# M401H.net
KiCad netlist of a schematic drawn in EAGLE
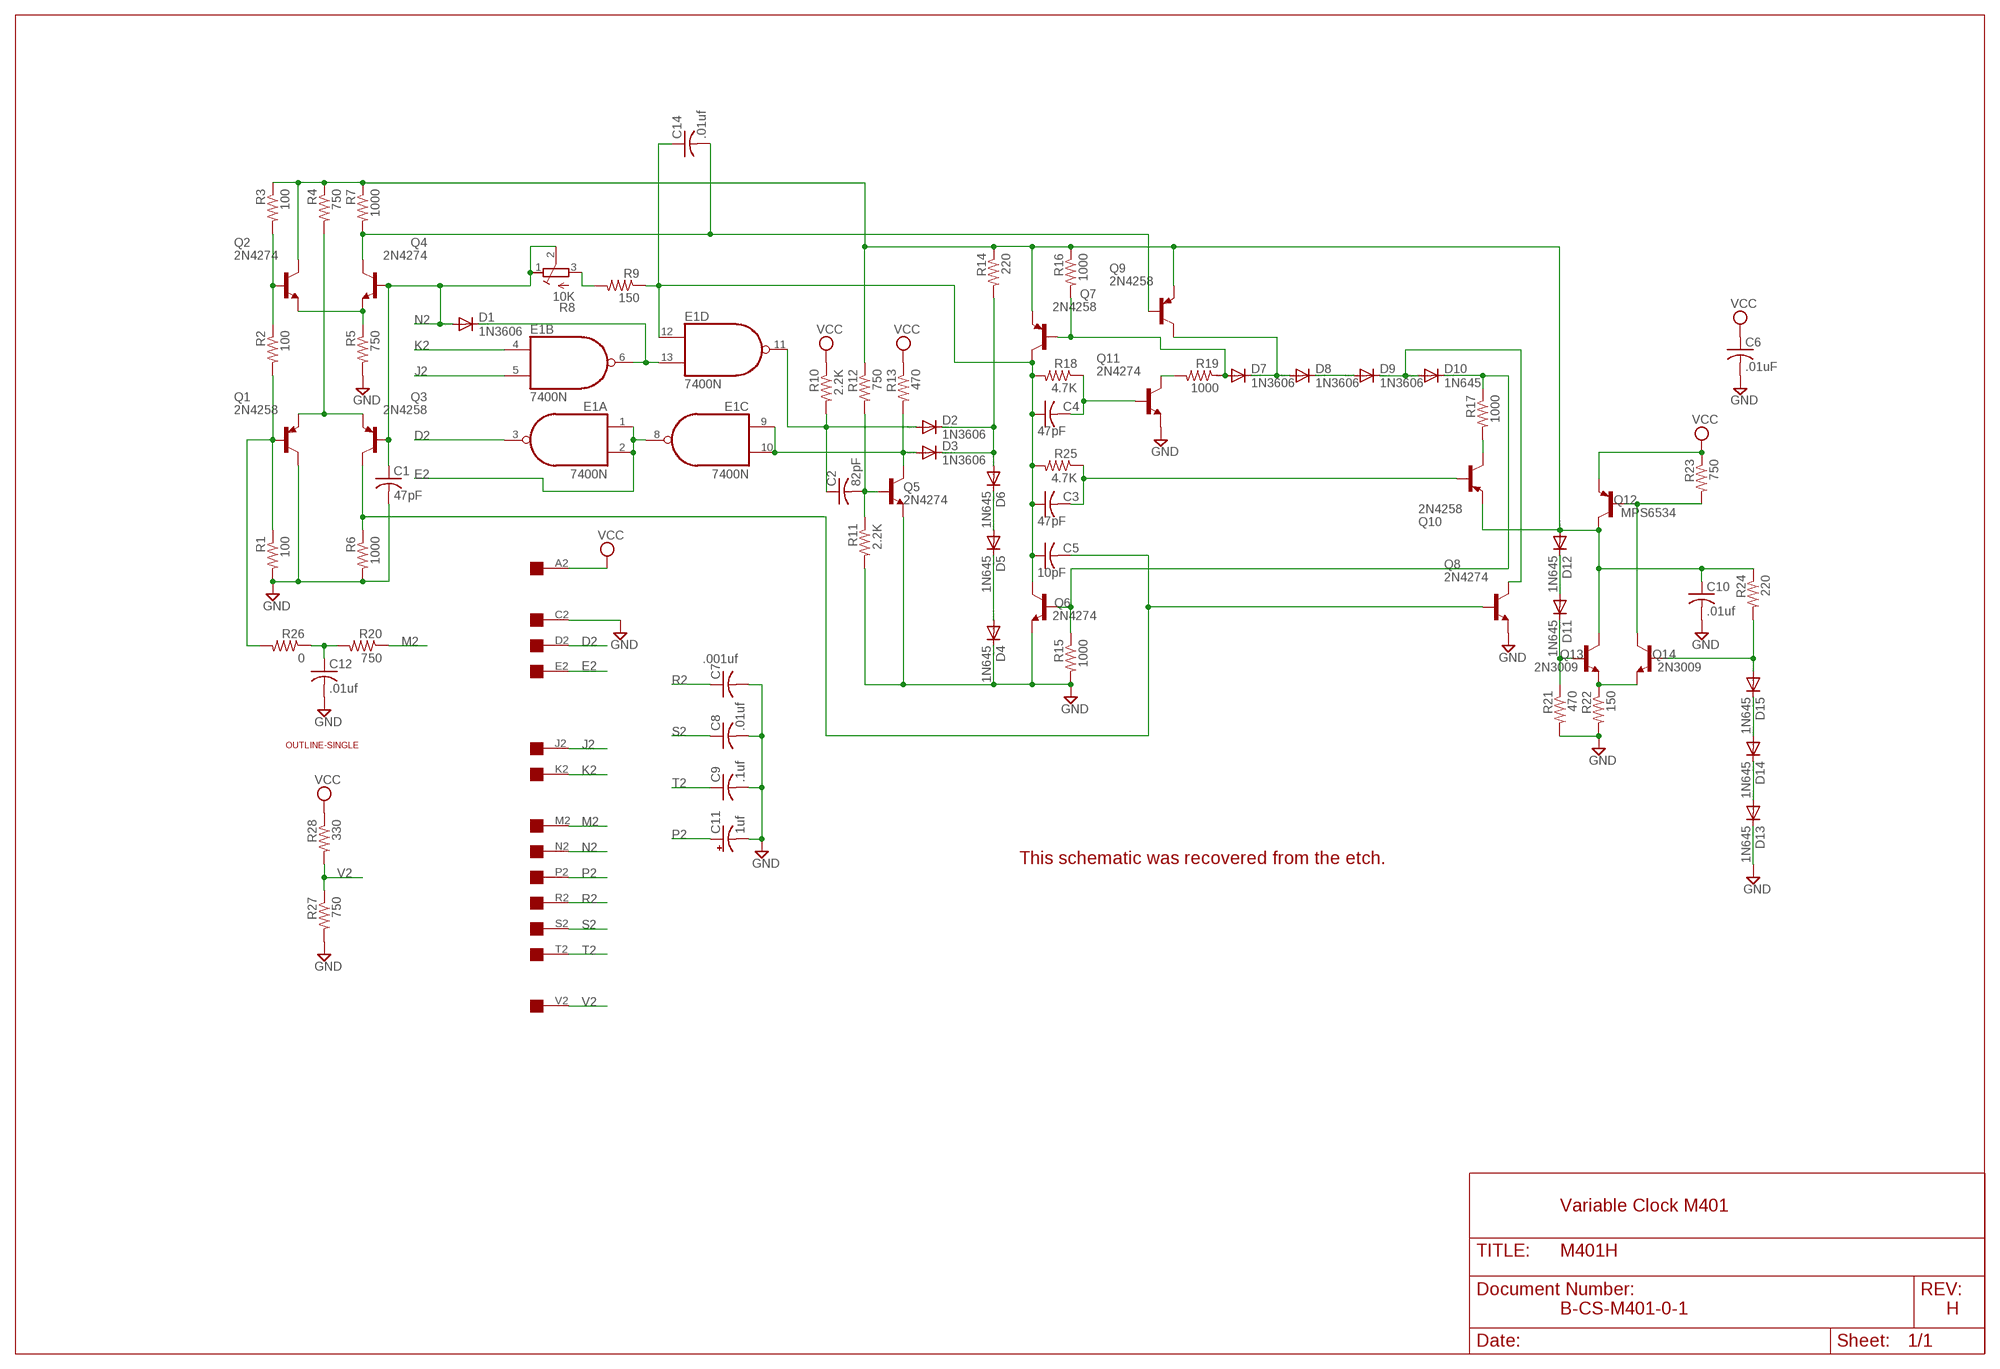
[diagram p0: schematic, sheet 1]

(export (version "E")
  (design (tool "Eeschema 10.0.6"))
  (components
    (comp (ref "C1")
      (value "47pF")
      (footprint "eagle-import:C075-032X103")
      (libsource (lib "eagle-import") (part "C-US075-032X103"))
    )
    (comp (ref "C2")
      (value "82pF")
      (footprint "eagle-import:C050-025X075")
      (libsource (lib "eagle-import") (part "C-US050-025X075"))
    )
    (comp (ref "C3")
      (value "47pF")
      (footprint "eagle-import:C050-025X075")
      (libsource (lib "eagle-import") (part "C-US050-025X075"))
    )
    (comp (ref "C4")
      (value "47pF")
      (footprint "eagle-import:C050-025X075")
      (libsource (lib "eagle-import") (part "C-US050-025X075"))
    )
    (comp (ref "C5")
      (value "10pF")
      (footprint "eagle-import:C050-025X075")
      (libsource (lib "eagle-import") (part "C-US050-025X075"))
    )
    (comp (ref "C6")
      (value ".01uF")
      (footprint "eagle-import:C102-043X133")
      (libsource (lib "eagle-import") (part "C-US102-043X133"))
    )
    (comp (ref "C7")
      (value ".001uf")
      (footprint "eagle-import:C075-032X103")
      (libsource (lib "eagle-import") (part "C-US075-032X103"))
    )
    (comp (ref "C8")
      (value ".01uf")
      (footprint "eagle-import:C225-062X268")
      (libsource (lib "eagle-import") (part "C-US225-062X268"))
    )
    (comp (ref "C9")
      (value ".1uf")
      (footprint "eagle-import:C275-093X316")
      (libsource (lib "eagle-import") (part "C-US275-093X316"))
    )
    (comp (ref "C10")
      (value ".01uf")
      (footprint "eagle-import:C050-025X075")
      (libsource (lib "eagle-import") (part "C-US050-025X075"))
    )
    (comp (ref "C11")
      (value "1uf")
      (footprint "eagle-import:E15-5")
      (libsource (lib "eagle-import") (part "CPOL-USE15-5AXIAL"))
    )
    (comp (ref "C12")
      (value ".01uf")
      (footprint "eagle-import:C050-025X075")
      (libsource (lib "eagle-import") (part "C-US050-025X075"))
    )
    (comp (ref "C14")
      (value ".01uf")
      (footprint "eagle-import:C050-025X075")
      (libsource (lib "eagle-import") (part "C-US050-025X075"))
    )
    (comp (ref "D1")
      (value "1N3606")
      (footprint "eagle-import:DO35-10")
      (libsource (lib "eagle-import") (part "1N4148DO35-10"))
    )
    (comp (ref "D2")
      (value "1N3606")
      (footprint "eagle-import:DO35-10")
      (libsource (lib "eagle-import") (part "1N4148DO35-10"))
    )
    (comp (ref "D3")
      (value "1N3606")
      (footprint "eagle-import:DO35-10")
      (libsource (lib "eagle-import") (part "1N4148DO35-10"))
    )
    (comp (ref "D4")
      (value "1N645")
      (footprint "eagle-import:DO35-10")
      (libsource (lib "eagle-import") (part "1N4148DO35-10"))
    )
    (comp (ref "D5")
      (value "1N645")
      (footprint "eagle-import:DO35-10")
      (libsource (lib "eagle-import") (part "1N4148DO35-10"))
    )
    (comp (ref "D6")
      (value "1N645")
      (footprint "eagle-import:DO35-10")
      (libsource (lib "eagle-import") (part "1N4148DO35-10"))
    )
    (comp (ref "D7")
      (value "1N3606")
      (footprint "eagle-import:DO35-10")
      (libsource (lib "eagle-import") (part "1N4148DO35-10"))
    )
    (comp (ref "D8")
      (value "1N3606")
      (footprint "eagle-import:DO35-10")
      (libsource (lib "eagle-import") (part "1N4148DO35-10"))
    )
    (comp (ref "D9")
      (value "1N3606")
      (footprint "eagle-import:DO35-10")
      (libsource (lib "eagle-import") (part "1N4148DO35-10"))
    )
    (comp (ref "D10")
      (value "1N645")
      (footprint "eagle-import:DO35-10")
      (libsource (lib "eagle-import") (part "1N4148DO35-10"))
    )
    (comp (ref "D11")
      (value "1N645")
      (footprint "eagle-import:DO35-10")
      (libsource (lib "eagle-import") (part "1N4148DO35-10"))
    )
    (comp (ref "D12")
      (value "1N645")
      (footprint "eagle-import:DO35-10")
      (libsource (lib "eagle-import") (part "1N4148DO35-10"))
    )
    (comp (ref "D13")
      (value "1N645")
      (footprint "eagle-import:DO35-10")
      (libsource (lib "eagle-import") (part "1N4148DO35-10"))
    )
    (comp (ref "D14")
      (value "1N645")
      (footprint "eagle-import:DO35-10")
      (libsource (lib "eagle-import") (part "1N4148DO35-10"))
    )
    (comp (ref "D15")
      (value "1N645")
      (footprint "eagle-import:DO35-10")
      (libsource (lib "eagle-import") (part "1N4148DO35-10"))
    )
    (comp (ref "E1")
      (value "7400N")
      (footprint "eagle-import:DIL14")
      (libsource (lib "eagle-import") (part "7400N"))
    )
    (comp (ref "Q1")
      (value "2N4258")
      (footprint "eagle-import:TO39")
      (libsource (lib "eagle-import") (part "-PNP-TO39-EBC2N3637"))
    )
    (comp (ref "Q2")
      (value "2N4274")
      (footprint "eagle-import:TO39")
      (libsource (lib "eagle-import") (part "-NPN-TO39-EBC2N3019"))
    )
    (comp (ref "Q3")
      (value "2N4258")
      (footprint "eagle-import:TO39")
      (libsource (lib "eagle-import") (part "-PNP-TO39-EBC2N3637"))
    )
    (comp (ref "Q4")
      (value "2N4274")
      (footprint "eagle-import:TO39")
      (libsource (lib "eagle-import") (part "-NPN-TO39-EBC2N3019"))
    )
    (comp (ref "Q5")
      (value "2N4274")
      (footprint "eagle-import:TO39")
      (libsource (lib "eagle-import") (part "-NPN-TO39-EBC2N3019"))
    )
    (comp (ref "Q6")
      (value "2N4274")
      (footprint "eagle-import:TO39")
      (libsource (lib "eagle-import") (part "-NPN-TO39-EBC2N3019"))
    )
    (comp (ref "Q7")
      (value "2N4258")
      (footprint "eagle-import:TO39")
      (libsource (lib "eagle-import") (part "-PNP-TO39-EBC2N3637"))
    )
    (comp (ref "Q8")
      (value "2N4274")
      (footprint "eagle-import:TO39")
      (libsource (lib "eagle-import") (part "-NPN-TO39-EBC2N3019"))
    )
    (comp (ref "Q9")
      (value "2N4258")
      (footprint "eagle-import:TO39")
      (libsource (lib "eagle-import") (part "-PNP-TO39-EBC2N3637"))
    )
    (comp (ref "Q10")
      (value "2N4258")
      (footprint "eagle-import:TO39")
      (libsource (lib "eagle-import") (part "-PNP-TO39-EBC2N3637"))
    )
    (comp (ref "Q11")
      (value "2N4274")
      (footprint "eagle-import:TO39")
      (libsource (lib "eagle-import") (part "-NPN-TO39-EBC2N3019"))
    )
    (comp (ref "Q12")
      (value "MPS6534")
      (footprint "eagle-import:TO39")
      (libsource (lib "eagle-import") (part "-PNP-TO39-EBC2N3637"))
    )
    (comp (ref "Q13")
      (value "2N3009")
      (footprint "eagle-import:TO39")
      (libsource (lib "eagle-import") (part "-NPN-TO39-EBC2N3019"))
    )
    (comp (ref "Q14")
      (value "2N3009")
      (footprint "eagle-import:TO39")
      (libsource (lib "eagle-import") (part "-NPN-TO39-EBC2N3019"))
    )
    (comp (ref "R1")
      (value "100")
      (footprint "eagle-import:0207_10")
      (libsource (lib "eagle-import") (part "R-US_0207/10"))
    )
    (comp (ref "R2")
      (value "100")
      (footprint "eagle-import:0207_10")
      (libsource (lib "eagle-import") (part "R-US_0207/10"))
    )
    (comp (ref "R3")
      (value "100")
      (footprint "eagle-import:0207_10")
      (libsource (lib "eagle-import") (part "R-US_0207/10"))
    )
    (comp (ref "R4")
      (value "750")
      (footprint "eagle-import:0207_10")
      (libsource (lib "eagle-import") (part "R-US_0207/10"))
    )
    (comp (ref "R5")
      (value "750")
      (footprint "eagle-import:0207_10")
      (libsource (lib "eagle-import") (part "R-US_0207/10"))
    )
    (comp (ref "R6")
      (value "1000")
      (footprint "eagle-import:0207_10")
      (libsource (lib "eagle-import") (part "R-US_0207/10"))
    )
    (comp (ref "R7")
      (value "1000")
      (footprint "eagle-import:0207_10")
      (libsource (lib "eagle-import") (part "R-US_0207/10"))
    )
    (comp (ref "R8")
      (value "10K")
      (footprint "eagle-import:3006Y")
      (libsource (lib "eagle-import") (part "275P"))
    )
    (comp (ref "R9")
      (value "150")
      (footprint "eagle-import:0207_10")
      (libsource (lib "eagle-import") (part "R-US_0207/10"))
    )
    (comp (ref "R10")
      (value "2.2K")
      (footprint "eagle-import:0207_10")
      (libsource (lib "eagle-import") (part "R-US_0207/10"))
    )
    (comp (ref "R11")
      (value "2.2K")
      (footprint "eagle-import:0207_10")
      (libsource (lib "eagle-import") (part "R-US_0207/10"))
    )
    (comp (ref "R12")
      (value "750")
      (footprint "eagle-import:0207_10")
      (libsource (lib "eagle-import") (part "R-US_0207/10"))
    )
    (comp (ref "R13")
      (value "470")
      (footprint "eagle-import:0207_10")
      (libsource (lib "eagle-import") (part "R-US_0207/10"))
    )
    (comp (ref "R14")
      (value "220")
      (footprint "eagle-import:0207_10")
      (libsource (lib "eagle-import") (part "R-US_0207/10"))
    )
    (comp (ref "R15")
      (value "1000")
      (footprint "eagle-import:0207_10")
      (libsource (lib "eagle-import") (part "R-US_0207/10"))
    )
    (comp (ref "R16")
      (value "1000")
      (footprint "eagle-import:0207_10")
      (libsource (lib "eagle-import") (part "R-US_0207/10"))
    )
    (comp (ref "R17")
      (value "1000")
      (footprint "eagle-import:0207_10")
      (libsource (lib "eagle-import") (part "R-US_0207/10"))
    )
    (comp (ref "R18")
      (value "4.7K")
      (footprint "eagle-import:0207_10")
      (libsource (lib "eagle-import") (part "R-US_0207/10"))
    )
    (comp (ref "R19")
      (value "1000")
      (footprint "eagle-import:0207_10")
      (libsource (lib "eagle-import") (part "R-US_0207/10"))
    )
    (comp (ref "R20")
      (value "750")
      (footprint "eagle-import:0207_10")
      (libsource (lib "eagle-import") (part "R-US_0207/10"))
    )
    (comp (ref "R21")
      (value "470")
      (footprint "eagle-import:0207_10")
      (libsource (lib "eagle-import") (part "R-US_0207/10"))
    )
    (comp (ref "R22")
      (value "150")
      (footprint "eagle-import:0207_10")
      (libsource (lib "eagle-import") (part "R-US_0207/10"))
    )
    (comp (ref "R23")
      (value "750")
      (footprint "eagle-import:0207_10")
      (libsource (lib "eagle-import") (part "R-US_0207/10"))
    )
    (comp (ref "R24")
      (value "220")
      (footprint "eagle-import:0207_10")
      (libsource (lib "eagle-import") (part "R-US_0207/10"))
    )
    (comp (ref "R25")
      (value "4.7K")
      (footprint "eagle-import:0207_10")
      (libsource (lib "eagle-import") (part "R-US_0207/10"))
    )
    (comp (ref "R26")
      (value "0")
      (footprint "eagle-import:0207_10")
      (libsource (lib "eagle-import") (part "R-US_0207/10"))
    )
    (comp (ref "R27")
      (value "750")
      (footprint "eagle-import:0207_10")
      (libsource (lib "eagle-import") (part "R-US_0207/10"))
    )
    (comp (ref "R28")
      (value "330")
      (footprint "eagle-import:0207_10")
      (libsource (lib "eagle-import") (part "R-US_0207/10"))
    )
    (comp (ref "U$1")
      (value "OUTLINE-SINGLE")
      (footprint "eagle-import:SINGLE")
      (libsource (lib "eagle-import") (part "OUTLINE-SINGLE"))
    )
    (comp (ref "U$2")
      (value "EDGE-1")
      (footprint "eagle-import:EDGE-CON1")
      (libsource (lib "eagle-import") (part "EDGE-1"))
    )
  )
  (nets
    (net (code "1") (name "/D2") (class "Default")
      (node (ref "E1") (pin "3") (pinfunction "O_3") (pintype "output"))
      (node (ref "U$2") (pin "D2") (pinfunction "1_D2") (pintype "bidirectional"))
    )
    (net (code "2") (name "/E2") (class "Default")
      (node (ref "E1") (pin "1") (pinfunction "I0_1") (pintype "input"))
      (node (ref "E1") (pin "2") (pinfunction "I1_2") (pintype "input"))
      (node (ref "E1") (pin "8") (pinfunction "O_8") (pintype "output"))
      (node (ref "U$2") (pin "E2") (pinfunction "1_E2") (pintype "bidirectional"))
    )
    (net (code "3") (name "/J2") (class "Default")
      (node (ref "E1") (pin "5") (pinfunction "I1_5") (pintype "input"))
      (node (ref "U$2") (pin "J2") (pinfunction "1_J2") (pintype "bidirectional"))
    )
    (net (code "4") (name "/K2") (class "Default")
      (node (ref "E1") (pin "4") (pinfunction "I0_4") (pintype "input"))
      (node (ref "U$2") (pin "K2") (pinfunction "1_K2") (pintype "bidirectional"))
    )
    (net (code "5") (name "/M2") (class "Default")
      (node (ref "R20") (pin "1") (pinfunction "1_1") (pintype "passive"))
      (node (ref "U$2") (pin "M2") (pinfunction "1_M2") (pintype "bidirectional"))
    )
    (net (code "6") (name "/N2") (class "Default")
      (node (ref "C1") (pin "1") (pinfunction "1_1") (pintype "passive"))
      (node (ref "D1") (pin "A") (pinfunction "A_A") (pintype "passive"))
      (node (ref "Q3") (pin "2") (pinfunction "B_2") (pintype "passive"))
      (node (ref "Q4") (pin "2") (pinfunction "B_2") (pintype "passive"))
      (node (ref "R8") (pin "1") (pinfunction "A_1") (pintype "passive"))
      (node (ref "R8") (pin "2") (pinfunction "S_2") (pintype "passive"))
      (node (ref "U$2") (pin "N2") (pinfunction "1_N2") (pintype "bidirectional"))
    )
    (net (code "7") (name "/P2") (class "Default")
      (node (ref "C11") (pin "+") (pinfunction "+_+") (pintype "passive"))
      (node (ref "U$2") (pin "P2") (pinfunction "1_P2") (pintype "bidirectional"))
    )
    (net (code "8") (name "/R2") (class "Default")
      (node (ref "C7") (pin "1") (pinfunction "1_1") (pintype "passive"))
      (node (ref "U$2") (pin "R2") (pinfunction "1_R2") (pintype "bidirectional"))
    )
    (net (code "9") (name "/S2") (class "Default")
      (node (ref "C8") (pin "1") (pinfunction "1_1") (pintype "passive"))
      (node (ref "U$2") (pin "S2") (pinfunction "1_S2") (pintype "bidirectional"))
    )
    (net (code "10") (name "/T2") (class "Default")
      (node (ref "C9") (pin "1") (pinfunction "1_1") (pintype "passive"))
      (node (ref "U$2") (pin "T2") (pinfunction "1_T2") (pintype "bidirectional"))
    )
    (net (code "11") (name "/V2") (class "Default")
      (node (ref "R27") (pin "1") (pinfunction "1_1") (pintype "passive"))
      (node (ref "R28") (pin "2") (pinfunction "2_2") (pintype "passive"))
      (node (ref "U$2") (pin "V2") (pinfunction "1_V2") (pintype "bidirectional"))
    )
    (net (code "12") (name "GND") (class "Default")
      (node (ref "C1") (pin "2") (pinfunction "2_2") (pintype "passive"))
      (node (ref "C10") (pin "2") (pinfunction "2_2") (pintype "passive"))
      (node (ref "C11") (pin "-") (pinfunction "-_-") (pintype "passive"))
      (node (ref "C12") (pin "2") (pinfunction "2_2") (pintype "passive"))
      (node (ref "C6") (pin "2") (pinfunction "2_2") (pintype "passive"))
      (node (ref "C7") (pin "2") (pinfunction "2_2") (pintype "passive"))
      (node (ref "C8") (pin "2") (pinfunction "2_2") (pintype "passive"))
      (node (ref "C9") (pin "2") (pinfunction "2_2") (pintype "passive"))
      (node (ref "D13") (pin "C") (pinfunction "C_C") (pintype "passive"))
      (node (ref "D4") (pin "C") (pinfunction "C_C") (pintype "passive"))
      (node (ref "Q1") (pin "3") (pinfunction "C_3") (pintype "passive"))
      (node (ref "Q11") (pin "1") (pinfunction "E_1") (pintype "passive"))
      (node (ref "Q5") (pin "1") (pinfunction "E_1") (pintype "passive"))
      (node (ref "Q6") (pin "1") (pinfunction "E_1") (pintype "passive"))
      (node (ref "Q8") (pin "1") (pinfunction "E_1") (pintype "passive"))
      (node (ref "R1") (pin "2") (pinfunction "2_2") (pintype "passive"))
      (node (ref "R11") (pin "2") (pinfunction "2_2") (pintype "passive"))
      (node (ref "R15") (pin "2") (pinfunction "2_2") (pintype "passive"))
      (node (ref "R21") (pin "2") (pinfunction "2_2") (pintype "passive"))
      (node (ref "R22") (pin "2") (pinfunction "2_2") (pintype "passive"))
      (node (ref "R27") (pin "2") (pinfunction "2_2") (pintype "passive"))
      (node (ref "R5") (pin "2") (pinfunction "2_2") (pintype "passive"))
      (node (ref "R6") (pin "2") (pinfunction "2_2") (pintype "passive"))
      (node (ref "U$2") (pin "C2") (pinfunction "1_C2") (pintype "bidirectional"))
    )
    (net (code "13") (name "Net-(C12-Pad1)") (class "Default")
      (node (ref "C12") (pin "1") (pinfunction "1_1") (pintype "passive"))
      (node (ref "R20") (pin "2") (pinfunction "2_2") (pintype "passive"))
      (node (ref "R26") (pin "1") (pinfunction "1_1") (pintype "passive"))
    )
    (net (code "14") (name "Net-(D2-PadC)") (class "Default")
      (node (ref "D2") (pin "C") (pinfunction "C_C") (pintype "passive"))
      (node (ref "D3") (pin "C") (pinfunction "C_C") (pintype "passive"))
      (node (ref "D6") (pin "A") (pinfunction "A_A") (pintype "passive"))
      (node (ref "R14") (pin "2") (pinfunction "2_2") (pintype "passive"))
    )
    (net (code "15") (name "Net-(D4-PadA)") (class "Default")
      (node (ref "D4") (pin "A") (pinfunction "A_A") (pintype "passive"))
      (node (ref "D5") (pin "C") (pinfunction "C_C") (pintype "passive"))
    )
    (net (code "16") (name "Net-(D5-PadA)") (class "Default")
      (node (ref "D5") (pin "A") (pinfunction "A_A") (pintype "passive"))
      (node (ref "D6") (pin "C") (pinfunction "C_C") (pintype "passive"))
    )
    (net (code "17") (name "Net-(D8-PadC)") (class "Default")
      (node (ref "D8") (pin "C") (pinfunction "C_C") (pintype "passive"))
      (node (ref "D9") (pin "A") (pinfunction "A_A") (pintype "passive"))
    )
    (net (code "18") (name "Net-(D11-PadA)") (class "Default")
      (node (ref "D11") (pin "A") (pinfunction "A_A") (pintype "passive"))
      (node (ref "D12") (pin "C") (pinfunction "C_C") (pintype "passive"))
    )
    (net (code "19") (name "Net-(D13-PadA)") (class "Default")
      (node (ref "D13") (pin "A") (pinfunction "A_A") (pintype "passive"))
      (node (ref "D14") (pin "C") (pinfunction "C_C") (pintype "passive"))
    )
    (net (code "20") (name "Net-(D14-PadA)") (class "Default")
      (node (ref "D14") (pin "A") (pinfunction "A_A") (pintype "passive"))
      (node (ref "D15") (pin "C") (pinfunction "C_C") (pintype "passive"))
    )
    (net (code "21") (name "Net-(E1B-O)") (class "Default")
      (node (ref "D1") (pin "C") (pinfunction "C_C") (pintype "passive"))
      (node (ref "E1") (pin "13") (pinfunction "I1_13") (pintype "input"))
      (node (ref "E1") (pin "6") (pinfunction "O_6") (pintype "output"))
    )
    (net (code "22") (name "Net-(E1C-I0)") (class "Default")
      (node (ref "D3") (pin "A") (pinfunction "A_A") (pintype "passive"))
      (node (ref "E1") (pin "10") (pinfunction "I1_10") (pintype "input"))
      (node (ref "E1") (pin "9") (pinfunction "I0_9") (pintype "input"))
      (node (ref "Q5") (pin "3") (pinfunction "C_3") (pintype "passive"))
      (node (ref "R13") (pin "2") (pinfunction "2_2") (pintype "passive"))
    )
    (net (code "23") (name "Net-(E1D-I0)") (class "Default")
      (node (ref "C14") (pin "1") (pinfunction "1_1") (pintype "passive"))
      (node (ref "C3") (pin "1") (pinfunction "1_1") (pintype "passive"))
      (node (ref "C4") (pin "1") (pinfunction "1_1") (pintype "passive"))
      (node (ref "C5") (pin "1") (pinfunction "1_1") (pintype "passive"))
      (node (ref "E1") (pin "12") (pinfunction "I0_12") (pintype "input"))
      (node (ref "Q6") (pin "3") (pinfunction "C_3") (pintype "passive"))
      (node (ref "Q7") (pin "3") (pinfunction "C_3") (pintype "passive"))
      (node (ref "R18") (pin "2") (pinfunction "2_2") (pintype "passive"))
      (node (ref "R25") (pin "2") (pinfunction "2_2") (pintype "passive"))
      (node (ref "R9") (pin "1") (pinfunction "1_1") (pintype "passive"))
    )
    (net (code "24") (name "Net-(E1D-O)") (class "Default")
      (node (ref "C2") (pin "1") (pinfunction "1_1") (pintype "passive"))
      (node (ref "D2") (pin "A") (pinfunction "A_A") (pintype "passive"))
      (node (ref "E1") (pin "11") (pinfunction "O_11") (pintype "output"))
      (node (ref "R10") (pin "2") (pinfunction "2_2") (pintype "passive"))
    )
    (net (code "25") (name "Net-(Q1-B)") (class "Default")
      (node (ref "Q1") (pin "2") (pinfunction "B_2") (pintype "passive"))
      (node (ref "R1") (pin "1") (pinfunction "1_1") (pintype "passive"))
      (node (ref "R2") (pin "2") (pinfunction "2_2") (pintype "passive"))
      (node (ref "R26") (pin "2") (pinfunction "2_2") (pintype "passive"))
    )
    (net (code "26") (name "Net-(Q1-E)") (class "Default")
      (node (ref "Q1") (pin "1") (pinfunction "E_1") (pintype "passive"))
      (node (ref "Q3") (pin "1") (pinfunction "E_1") (pintype "passive"))
      (node (ref "R4") (pin "2") (pinfunction "2_2") (pintype "passive"))
    )
    (net (code "27") (name "Net-(Q2-B)") (class "Default")
      (node (ref "Q2") (pin "2") (pinfunction "B_2") (pintype "passive"))
      (node (ref "R2") (pin "1") (pinfunction "1_1") (pintype "passive"))
      (node (ref "R3") (pin "2") (pinfunction "2_2") (pintype "passive"))
    )
    (net (code "28") (name "Net-(Q2-E)") (class "Default")
      (node (ref "Q2") (pin "1") (pinfunction "E_1") (pintype "passive"))
      (node (ref "Q4") (pin "1") (pinfunction "E_1") (pintype "passive"))
      (node (ref "R5") (pin "1") (pinfunction "1_1") (pintype "passive"))
    )
    (net (code "29") (name "Net-(Q3-C)") (class "Default")
      (node (ref "C5") (pin "2") (pinfunction "2_2") (pintype "passive"))
      (node (ref "Q3") (pin "3") (pinfunction "C_3") (pintype "passive"))
      (node (ref "Q8") (pin "2") (pinfunction "B_2") (pintype "passive"))
      (node (ref "R6") (pin "1") (pinfunction "1_1") (pintype "passive"))
    )
    (net (code "30") (name "Net-(Q4-C)") (class "Default")
      (node (ref "C14") (pin "2") (pinfunction "2_2") (pintype "passive"))
      (node (ref "Q4") (pin "3") (pinfunction "C_3") (pintype "passive"))
      (node (ref "Q9") (pin "2") (pinfunction "B_2") (pintype "passive"))
      (node (ref "R7") (pin "2") (pinfunction "2_2") (pintype "passive"))
    )
    (net (code "31") (name "Net-(Q5-B)") (class "Default")
      (node (ref "C2") (pin "2") (pinfunction "2_2") (pintype "passive"))
      (node (ref "Q5") (pin "2") (pinfunction "B_2") (pintype "passive"))
      (node (ref "R11") (pin "1") (pinfunction "1_1") (pintype "passive"))
      (node (ref "R12") (pin "2") (pinfunction "2_2") (pintype "passive"))
    )
    (net (code "32") (name "Net-(Q6-B)") (class "Default")
      (node (ref "D10") (pin "C") (pinfunction "C_C") (pintype "passive"))
      (node (ref "Q6") (pin "2") (pinfunction "B_2") (pintype "passive"))
      (node (ref "R15") (pin "1") (pinfunction "1_1") (pintype "passive"))
      (node (ref "R17") (pin "1") (pinfunction "1_1") (pintype "passive"))
    )
    (net (code "33") (name "Net-(Q7-B)") (class "Default")
      (node (ref "D7") (pin "A") (pinfunction "A_A") (pintype "passive"))
      (node (ref "Q7") (pin "2") (pinfunction "B_2") (pintype "passive"))
      (node (ref "R16") (pin "2") (pinfunction "2_2") (pintype "passive"))
      (node (ref "R19") (pin "1") (pinfunction "1_1") (pintype "passive"))
    )
    (net (code "34") (name "Net-(Q8-C)") (class "Default")
      (node (ref "D10") (pin "A") (pinfunction "A_A") (pintype "passive"))
      (node (ref "D9") (pin "C") (pinfunction "C_C") (pintype "passive"))
      (node (ref "Q8") (pin "3") (pinfunction "C_3") (pintype "passive"))
    )
    (net (code "35") (name "Net-(Q9-C)") (class "Default")
      (node (ref "D7") (pin "C") (pinfunction "C_C") (pintype "passive"))
      (node (ref "D8") (pin "A") (pinfunction "A_A") (pintype "passive"))
      (node (ref "Q9") (pin "3") (pinfunction "C_3") (pintype "passive"))
    )
    (net (code "36") (name "Net-(Q10-B)") (class "Default")
      (node (ref "C3") (pin "2") (pinfunction "2_2") (pintype "passive"))
      (node (ref "Q10") (pin "2") (pinfunction "B_2") (pintype "passive"))
      (node (ref "R25") (pin "1") (pinfunction "1_1") (pintype "passive"))
    )
    (net (code "37") (name "Net-(Q10-C)") (class "Default")
      (node (ref "Q10") (pin "3") (pinfunction "C_3") (pintype "passive"))
      (node (ref "R17") (pin "2") (pinfunction "2_2") (pintype "passive"))
    )
    (net (code "38") (name "Net-(Q10-E)") (class "Default")
      (node (ref "C10") (pin "1") (pinfunction "1_1") (pintype "passive"))
      (node (ref "D12") (pin "A") (pinfunction "A_A") (pintype "passive"))
      (node (ref "Q10") (pin "1") (pinfunction "E_1") (pintype "passive"))
      (node (ref "Q12") (pin "3") (pinfunction "C_3") (pintype "passive"))
      (node (ref "Q13") (pin "3") (pinfunction "C_3") (pintype "passive"))
      (node (ref "Q2") (pin "3") (pinfunction "C_3") (pintype "passive"))
      (node (ref "Q7") (pin "1") (pinfunction "E_1") (pintype "passive"))
      (node (ref "Q9") (pin "1") (pinfunction "E_1") (pintype "passive"))
      (node (ref "R12") (pin "1") (pinfunction "1_1") (pintype "passive"))
      (node (ref "R14") (pin "1") (pinfunction "1_1") (pintype "passive"))
      (node (ref "R16") (pin "1") (pinfunction "1_1") (pintype "passive"))
      (node (ref "R24") (pin "1") (pinfunction "1_1") (pintype "passive"))
      (node (ref "R3") (pin "1") (pinfunction "1_1") (pintype "passive"))
      (node (ref "R4") (pin "1") (pinfunction "1_1") (pintype "passive"))
      (node (ref "R7") (pin "1") (pinfunction "1_1") (pintype "passive"))
    )
    (net (code "39") (name "Net-(Q11-B)") (class "Default")
      (node (ref "C4") (pin "2") (pinfunction "2_2") (pintype "passive"))
      (node (ref "Q11") (pin "2") (pinfunction "B_2") (pintype "passive"))
      (node (ref "R18") (pin "1") (pinfunction "1_1") (pintype "passive"))
    )
    (net (code "40") (name "Net-(Q11-C)") (class "Default")
      (node (ref "Q11") (pin "3") (pinfunction "C_3") (pintype "passive"))
      (node (ref "R19") (pin "2") (pinfunction "2_2") (pintype "passive"))
    )
    (net (code "41") (name "Net-(Q12-B)") (class "Default")
      (node (ref "Q12") (pin "2") (pinfunction "B_2") (pintype "passive"))
      (node (ref "Q14") (pin "3") (pinfunction "C_3") (pintype "passive"))
      (node (ref "R23") (pin "2") (pinfunction "2_2") (pintype "passive"))
    )
    (net (code "42") (name "Net-(Q13-B)") (class "Default")
      (node (ref "D11") (pin "C") (pinfunction "C_C") (pintype "passive"))
      (node (ref "Q13") (pin "2") (pinfunction "B_2") (pintype "passive"))
      (node (ref "R21") (pin "1") (pinfunction "1_1") (pintype "passive"))
    )
    (net (code "43") (name "Net-(Q13-E)") (class "Default")
      (node (ref "Q13") (pin "1") (pinfunction "E_1") (pintype "passive"))
      (node (ref "Q14") (pin "1") (pinfunction "E_1") (pintype "passive"))
      (node (ref "R22") (pin "1") (pinfunction "1_1") (pintype "passive"))
    )
    (net (code "44") (name "Net-(Q14-B)") (class "Default")
      (node (ref "D15") (pin "A") (pinfunction "A_A") (pintype "passive"))
      (node (ref "Q14") (pin "2") (pinfunction "B_2") (pintype "passive"))
      (node (ref "R24") (pin "2") (pinfunction "2_2") (pintype "passive"))
    )
    (net (code "45") (name "Net-(R8-E)") (class "Default")
      (node (ref "R8") (pin "3") (pinfunction "E_3") (pintype "passive"))
      (node (ref "R9") (pin "2") (pinfunction "2_2") (pintype "passive"))
    )
    (net (code "46") (name "VCC") (class "Default")
      (node (ref "C6") (pin "1") (pinfunction "1_1") (pintype "passive"))
      (node (ref "Q12") (pin "1") (pinfunction "E_1") (pintype "passive"))
      (node (ref "R10") (pin "1") (pinfunction "1_1") (pintype "passive"))
      (node (ref "R13") (pin "1") (pinfunction "1_1") (pintype "passive"))
      (node (ref "R23") (pin "1") (pinfunction "1_1") (pintype "passive"))
      (node (ref "R28") (pin "1") (pinfunction "1_1") (pintype "passive"))
      (node (ref "U$2") (pin "A2") (pinfunction "1_A2") (pintype "bidirectional"))
    )
  )
)
